# 10_LCDC_MAC_I2S1_JTAG.net
KiCad netlist of a schematic drawn in Altium Designer
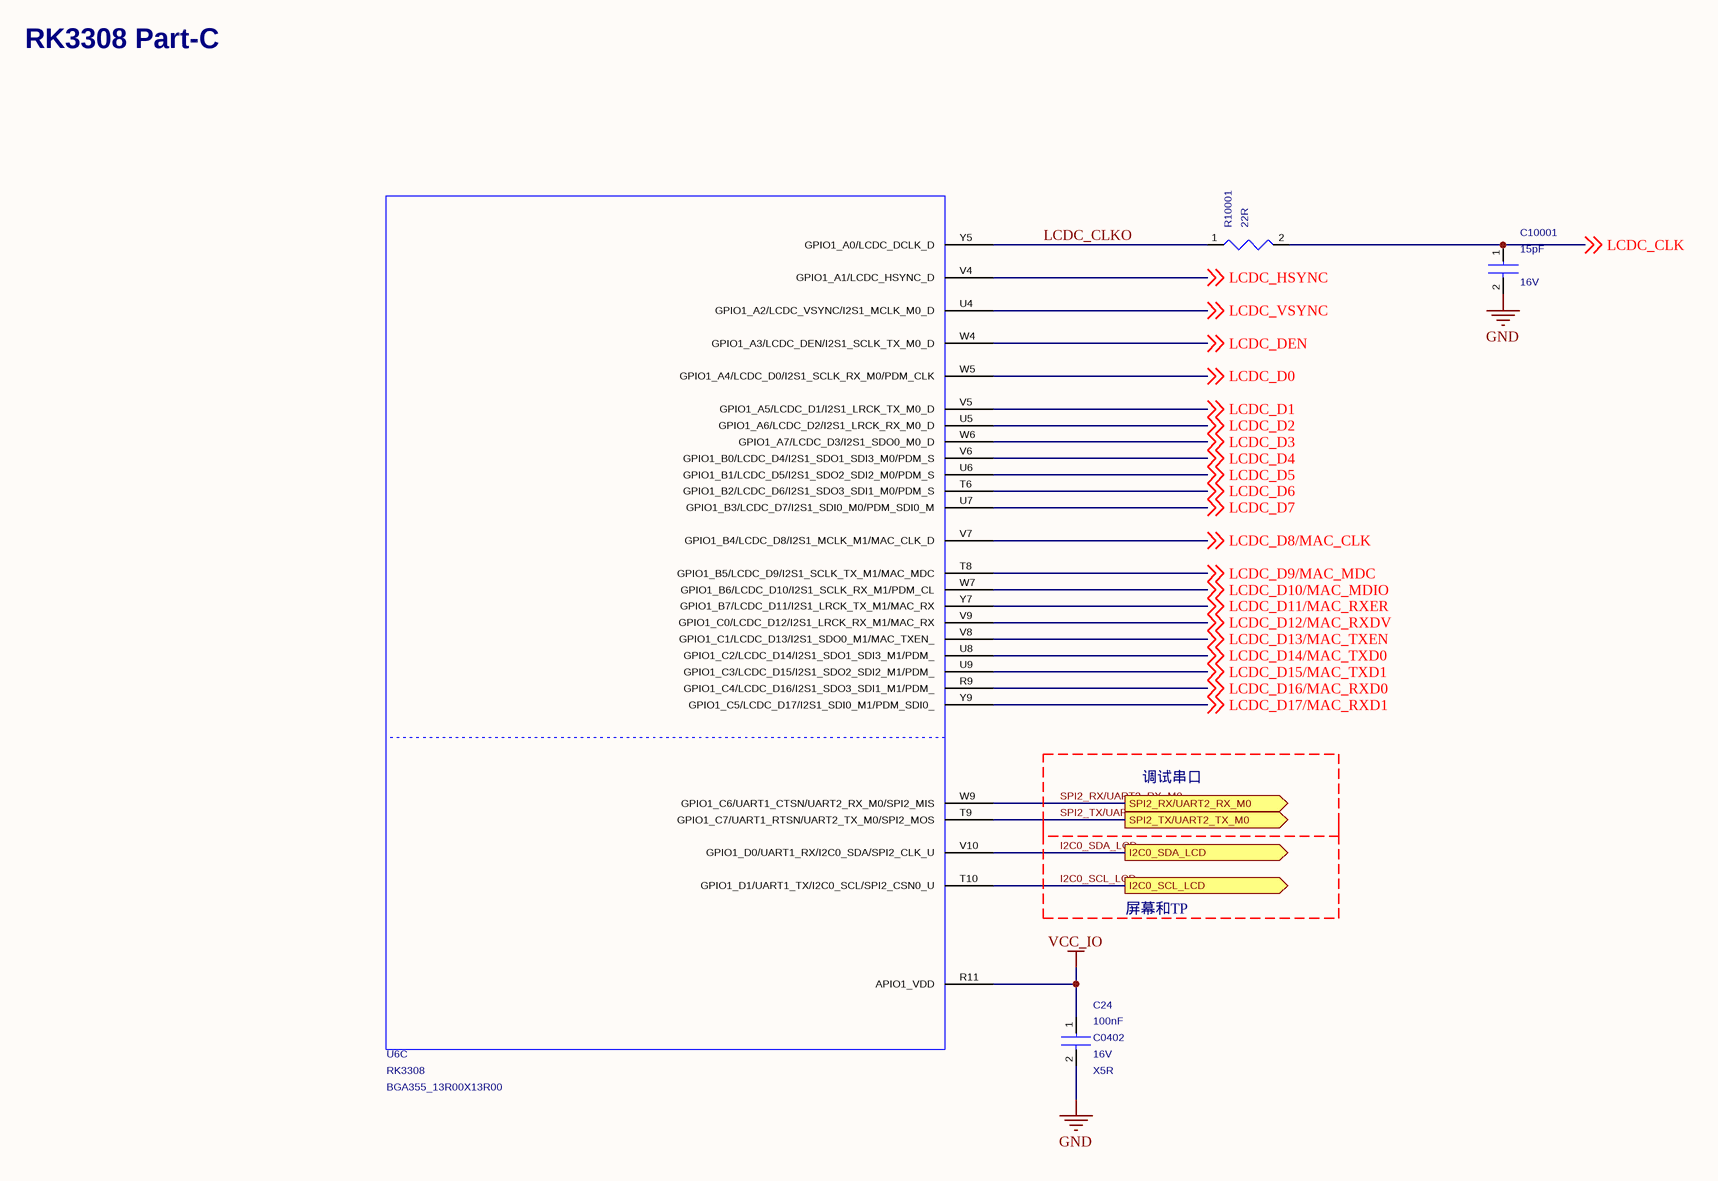
[diagram p0: 10_LCDC_MAC_I2S1_JTAG.SchDoc]

(export (version "E")
  (design (tool "Eeschema 10.0.6"))
  (components
    (comp (ref "C24")
      (value "100nF")
      (footprint "C0402")
      (description "cap,100.00nF,+/-10%,16V,X5R,C0402")
      (fields
        (field (name "PCB DECAL") "C0402")
        (field (name "DIELECTRIC") "X5R")
        (field (name "VOLTAGE") "16V")
        (field (name "TOLERANCE") "10%")
        (field (name "MANUFACTURER") "TDK")
        (field (name "CREATED_BY") "JJJ")
      )
      (libsource (lib "*") (part "CAP_NP_2"))
    )
    (comp (ref "C10001")
      (value "15pF")
      (footprint "C0402")
      (description "cap,15pF,+/-10%,16V,X5R,C0402")
      (fields
        (field (name "VOLTAGE") "16V")
        (field (name "TOLERANCE") "10%")
        (field (name "MANUFACTURER") "TDK")
        (field (name "CREATED_BY") "JJJ")
      )
      (libsource (lib "*") (part "CAP_NP_2"))
    )
    (comp (ref "R10001")
      (value "22R")
      (footprint "R0402")
      (description "?用厚膜电阻,22R,+/-1%,R0402,1/16W.")
      (fields
        (field (name "MANUFACTURER") "YAGEO")
        (field (name "TOLERANCE") "1%")
        (field (name "CREATED_BY") "YTL")
      )
      (libsource (lib "*") (part "RESISTOR"))
    )
    (comp (ref "U6")
      (value "RK3308")
      (footprint "BGA355_13R00X13R00")
      (fields (field (name "MANUFACTURER") "ROCKCHIP") (field (name "PCB DECAL") "BGA355_13R00X13R00"))
      (libsource (lib "RK3308SCH") (part "RK3308"))
    )
  )
  (nets
    (net (code "1") (name "/I2C0_SCL_LCD") (class "Default")
      (node (ref "U6") (pin "T10") (pinfunction "GPIO1_D1/UART1_TX/I2C0_SCL/SPI2_CSN0_U_T10") (pintype "passive"))
    )
    (net (code "2") (name "/I2C0_SDA_LCD") (class "Default")
      (node (ref "U6") (pin "V10") (pinfunction "GPIO1_D0/UART1_RX/I2C0_SDA/SPI2_CLK_U_V10") (pintype "passive"))
    )
    (net (code "3") (name "/LCDC_CLKO") (class "Default")
      (node (ref "R10001") (pin "1") (pinfunction "1_1") (pintype "passive"))
      (node (ref "U6") (pin "Y5") (pinfunction "GPIO1_A0/LCDC_DCLK_D_Y5") (pintype "passive"))
    )
    (net (code "4") (name "/SPI2_RX{slash}UART2_RX_M0") (class "Default")
      (node (ref "U6") (pin "W9") (pinfunction "GPIO1_C6/UART1_CTSN/UART2_RX_M0/SPI2_MIS_W9") (pintype "passive"))
    )
    (net (code "5") (name "/SPI2_TX{slash}UART2_TX_M0") (class "Default")
      (node (ref "U6") (pin "T9") (pinfunction "GPIO1_C7/UART1_RTSN/UART2_TX_M0/SPI2_MOS_T9") (pintype "passive"))
    )
    (net (code "6") (name "GND") (class "Default")
      (node (ref "C10001") (pin "2") (pinfunction "2_2") (pintype "passive"))
      (node (ref "C24") (pin "2") (pinfunction "2_2") (pintype "passive"))
    )
    (net (code "7") (name "LCDC_CLK") (class "Default")
      (node (ref "C10001") (pin "1") (pinfunction "1_1") (pintype "passive"))
      (node (ref "R10001") (pin "2") (pinfunction "2_2") (pintype "passive"))
    )
    (net (code "8") (name "LCDC_D0") (class "Default")
      (node (ref "U6") (pin "W5") (pinfunction "GPIO1_A4/LCDC_D0/I2S1_SCLK_RX_M0/PDM_CLK_W5") (pintype "passive"))
    )
    (net (code "9") (name "LCDC_D1") (class "Default")
      (node (ref "U6") (pin "V5") (pinfunction "GPIO1_A5/LCDC_D1/I2S1_LRCK_TX_M0_D_V5") (pintype "passive"))
    )
    (net (code "10") (name "LCDC_D2") (class "Default")
      (node (ref "U6") (pin "U5") (pinfunction "GPIO1_A6/LCDC_D2/I2S1_LRCK_RX_M0_D_U5") (pintype "passive"))
    )
    (net (code "11") (name "LCDC_D3") (class "Default")
      (node (ref "U6") (pin "W6") (pinfunction "GPIO1_A7/LCDC_D3/I2S1_SDO0_M0_D_W6") (pintype "passive"))
    )
    (net (code "12") (name "LCDC_D4") (class "Default")
      (node (ref "U6") (pin "V6") (pinfunction "GPIO1_B0/LCDC_D4/I2S1_SDO1_SDI3_M0/PDM_S_V6") (pintype "passive"))
    )
    (net (code "13") (name "LCDC_D5") (class "Default")
      (node (ref "U6") (pin "U6") (pinfunction "GPIO1_B1/LCDC_D5/I2S1_SDO2_SDI2_M0/PDM_S_U6") (pintype "passive"))
    )
    (net (code "14") (name "LCDC_D6") (class "Default")
      (node (ref "U6") (pin "T6") (pinfunction "GPIO1_B2/LCDC_D6/I2S1_SDO3_SDI1_M0/PDM_S_T6") (pintype "passive"))
    )
    (net (code "15") (name "LCDC_D7") (class "Default")
      (node (ref "U6") (pin "U7") (pinfunction "GPIO1_B3/LCDC_D7/I2S1_SDI0_M0/PDM_SDI0_M_U7") (pintype "passive"))
    )
    (net (code "16") (name "LCDC_D8{slash}MAC_CLK") (class "Default")
      (node (ref "U6") (pin "V7") (pinfunction "GPIO1_B4/LCDC_D8/I2S1_MCLK_M1/MAC_CLK_D_V7") (pintype "passive"))
    )
    (net (code "17") (name "LCDC_D9{slash}MAC_MDC") (class "Default")
      (node (ref "U6") (pin "T8") (pinfunction "GPIO1_B5/LCDC_D9/I2S1_SCLK_TX_M1/MAC_MDC_T8") (pintype "passive"))
    )
    (net (code "18") (name "LCDC_D10{slash}MAC_MDIO") (class "Default")
      (node (ref "U6") (pin "W7") (pinfunction "GPIO1_B6/LCDC_D10/I2S1_SCLK_RX_M1/PDM_CL_W7") (pintype "passive"))
    )
    (net (code "19") (name "LCDC_D11{slash}MAC_RXER") (class "Default")
      (node (ref "U6") (pin "Y7") (pinfunction "GPIO1_B7/LCDC_D11/I2S1_LRCK_TX_M1/MAC_RX_Y7") (pintype "passive"))
    )
    (net (code "20") (name "LCDC_D12{slash}MAC_RXDV") (class "Default")
      (node (ref "U6") (pin "V9") (pinfunction "GPIO1_C0/LCDC_D12/I2S1_LRCK_RX_M1/MAC_RX_V9") (pintype "passive"))
    )
    (net (code "21") (name "LCDC_D13{slash}MAC_TXEN") (class "Default")
      (node (ref "U6") (pin "V8") (pinfunction "GPIO1_C1/LCDC_D13/I2S1_SDO0_M1/MAC_TXEN__V8") (pintype "passive"))
    )
    (net (code "22") (name "LCDC_D14{slash}MAC_TXD0") (class "Default")
      (node (ref "U6") (pin "U8") (pinfunction "GPIO1_C2/LCDC_D14/I2S1_SDO1_SDI3_M1/PDM__U8") (pintype "passive"))
    )
    (net (code "23") (name "LCDC_D15{slash}MAC_TXD1") (class "Default")
      (node (ref "U6") (pin "U9") (pinfunction "GPIO1_C3/LCDC_D15/I2S1_SDO2_SDI2_M1/PDM__U9") (pintype "passive"))
    )
    (net (code "24") (name "LCDC_D16{slash}MAC_RXD0") (class "Default")
      (node (ref "U6") (pin "R9") (pinfunction "GPIO1_C4/LCDC_D16/I2S1_SDO3_SDI1_M1/PDM__R9") (pintype "passive"))
    )
    (net (code "25") (name "LCDC_D17{slash}MAC_RXD1") (class "Default")
      (node (ref "U6") (pin "Y9") (pinfunction "GPIO1_C5/LCDC_D17/I2S1_SDI0_M1/PDM_SDI0__Y9") (pintype "passive"))
    )
    (net (code "26") (name "LCDC_DEN") (class "Default")
      (node (ref "U6") (pin "W4") (pinfunction "GPIO1_A3/LCDC_DEN/I2S1_SCLK_TX_M0_D_W4") (pintype "passive"))
    )
    (net (code "27") (name "LCDC_HSYNC") (class "Default")
      (node (ref "U6") (pin "V4") (pinfunction "GPIO1_A1/LCDC_HSYNC_D_V4") (pintype "passive"))
    )
    (net (code "28") (name "LCDC_VSYNC") (class "Default")
      (node (ref "U6") (pin "U4") (pinfunction "GPIO1_A2/LCDC_VSYNC/I2S1_MCLK_M0_D_U4") (pintype "passive"))
    )
    (net (code "29") (name "VCC_IO") (class "Default")
      (node (ref "C24") (pin "1") (pinfunction "1_1") (pintype "passive"))
      (node (ref "U6") (pin "R11") (pinfunction "APIO1_VDD_R11") (pintype "passive"))
    )
  )
)
